# PFC_drivers_v1.net
KiCad netlist of a schematic drawn in EAGLE
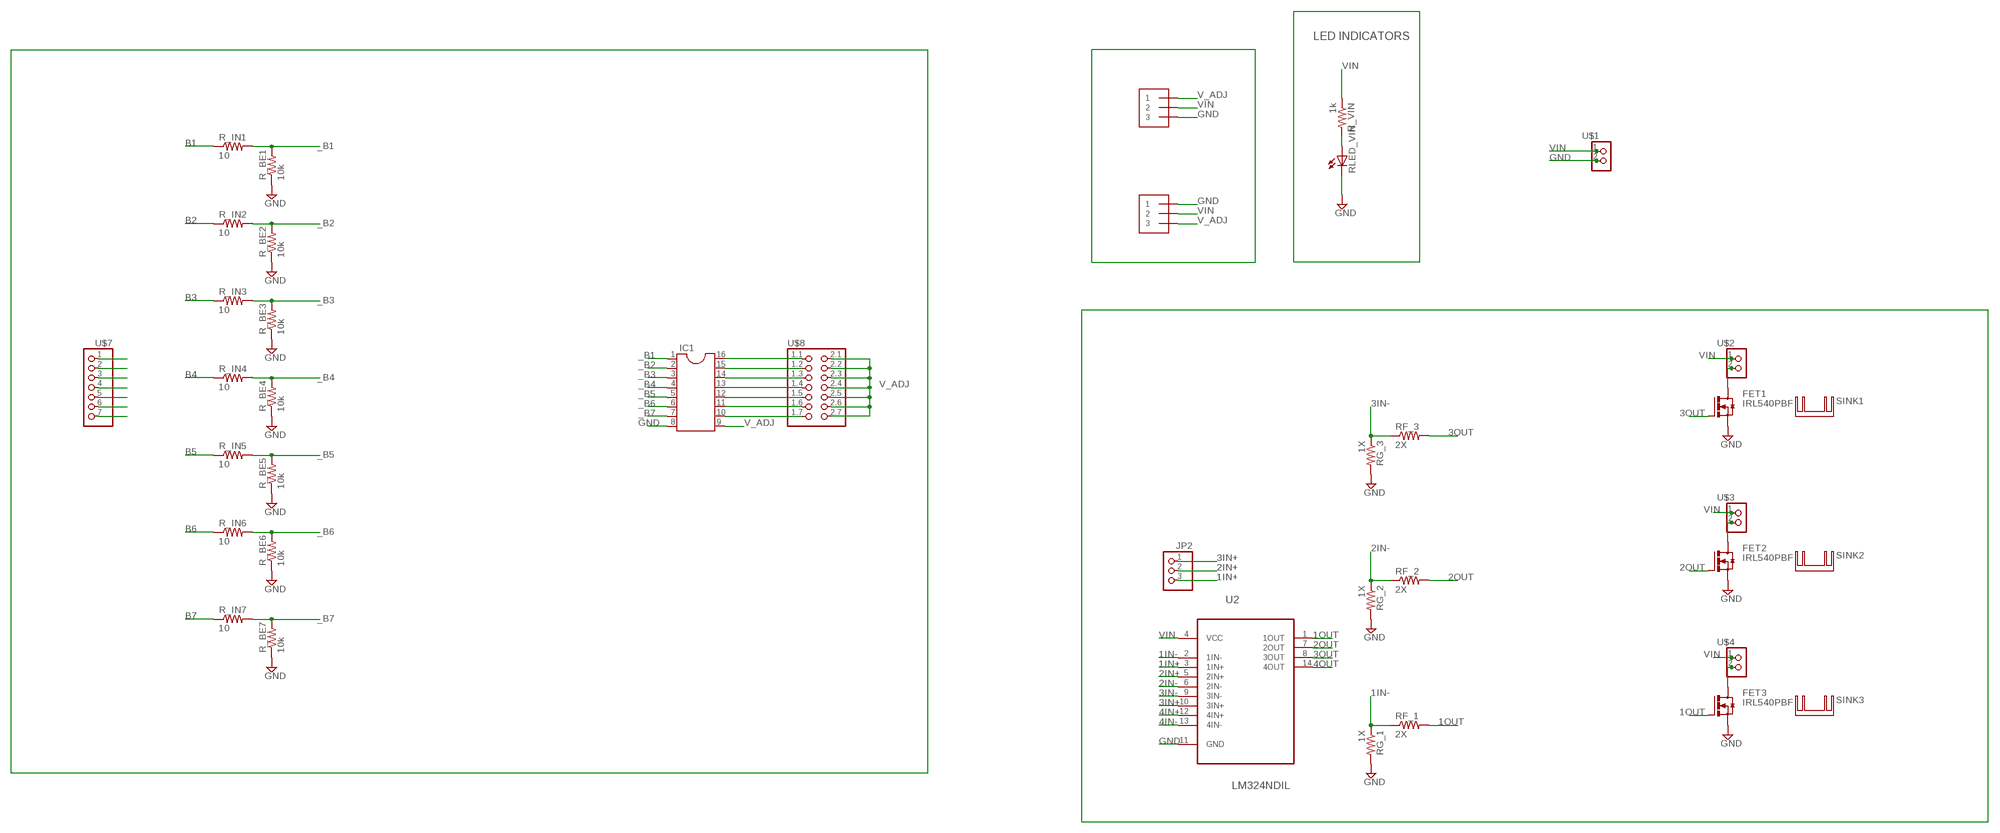
[diagram p0: schematic, sheet 1]

(export (version "E")
  (design (tool "Eeschema 10.0.6"))
  (components
    (comp (ref "FET1")
      (value "IRL540PBF")
      (footprint "eagle-import:TO220AV")
      (libsource (lib "eagle-import") (part "IRL540PBF"))
    )
    (comp (ref "FET2")
      (value "IRL540PBF")
      (footprint "eagle-import:TO220AV")
      (libsource (lib "eagle-import") (part "IRL540PBF"))
    )
    (comp (ref "FET3")
      (value "IRL540PBF")
      (footprint "eagle-import:TO220AV")
      (libsource (lib "eagle-import") (part "IRL540PBF"))
    )
    (comp (ref "IC1")
      (value "DIL16S")
      (footprint "eagle-import:SOCKET-16")
      (libsource (lib "eagle-import") (part "DIL16S"))
    )
    (comp (ref "JP2")
      (value "PINHD-1X3")
      (footprint "eagle-import:1X03")
      (libsource (lib "eagle-import") (part "PINHD-1X3"))
    )
    (comp (ref "RF_1")
      (value "2X")
      (footprint "eagle-import:R0603")
      (libsource (lib "eagle-import") (part "R-US_R0603"))
    )
    (comp (ref "RF_2")
      (value "2X")
      (footprint "eagle-import:R0603")
      (libsource (lib "eagle-import") (part "R-US_R0603"))
    )
    (comp (ref "RF_3")
      (value "2X")
      (footprint "eagle-import:R0603")
      (libsource (lib "eagle-import") (part "R-US_R0603"))
    )
    (comp (ref "RG_1")
      (value "1X")
      (footprint "eagle-import:R0603")
      (libsource (lib "eagle-import") (part "R-US_R0603"))
    )
    (comp (ref "RG_2")
      (value "1X")
      (footprint "eagle-import:R0603")
      (libsource (lib "eagle-import") (part "R-US_R0603"))
    )
    (comp (ref "RG_3")
      (value "1X")
      (footprint "eagle-import:R0603")
      (libsource (lib "eagle-import") (part "R-US_R0603"))
    )
    (comp (ref "RLED_VIN")
      (value "LEDCHIP-LED0603")
      (footprint "eagle-import:CHIP-LED0603")
      (libsource (lib "eagle-import") (part "LEDCHIP-LED0603"))
    )
    (comp (ref "R_BE1")
      (value "10k")
      (footprint "eagle-import:R0603")
      (libsource (lib "eagle-import") (part "R-US_R0603"))
    )
    (comp (ref "R_BE2")
      (value "10k")
      (footprint "eagle-import:R0603")
      (libsource (lib "eagle-import") (part "R-US_R0603"))
    )
    (comp (ref "R_BE3")
      (value "10k")
      (footprint "eagle-import:R0603")
      (libsource (lib "eagle-import") (part "R-US_R0603"))
    )
    (comp (ref "R_BE4")
      (value "10k")
      (footprint "eagle-import:R0603")
      (libsource (lib "eagle-import") (part "R-US_R0603"))
    )
    (comp (ref "R_BE5")
      (value "10k")
      (footprint "eagle-import:R0603")
      (libsource (lib "eagle-import") (part "R-US_R0603"))
    )
    (comp (ref "R_BE6")
      (value "10k")
      (footprint "eagle-import:R0603")
      (libsource (lib "eagle-import") (part "R-US_R0603"))
    )
    (comp (ref "R_BE7")
      (value "10k")
      (footprint "eagle-import:R0603")
      (libsource (lib "eagle-import") (part "R-US_R0603"))
    )
    (comp (ref "R_IN1")
      (value "10")
      (footprint "eagle-import:R0603")
      (libsource (lib "eagle-import") (part "R-US_R0603"))
    )
    (comp (ref "R_IN2")
      (value "10")
      (footprint "eagle-import:R0603")
      (libsource (lib "eagle-import") (part "R-US_R0603"))
    )
    (comp (ref "R_IN3")
      (value "10")
      (footprint "eagle-import:R0603")
      (libsource (lib "eagle-import") (part "R-US_R0603"))
    )
    (comp (ref "R_IN4")
      (value "10")
      (footprint "eagle-import:R0603")
      (libsource (lib "eagle-import") (part "R-US_R0603"))
    )
    (comp (ref "R_IN5")
      (value "10")
      (footprint "eagle-import:R0603")
      (libsource (lib "eagle-import") (part "R-US_R0603"))
    )
    (comp (ref "R_IN6")
      (value "10")
      (footprint "eagle-import:R0603")
      (libsource (lib "eagle-import") (part "R-US_R0603"))
    )
    (comp (ref "R_IN7")
      (value "10")
      (footprint "eagle-import:R0603")
      (libsource (lib "eagle-import") (part "R-US_R0603"))
    )
    (comp (ref "R_VIN")
      (value "1k")
      (footprint "eagle-import:R0603")
      (libsource (lib "eagle-import") (part "R-US_R0603"))
    )
    (comp (ref "SINK1")
      (value "FW1S")
      (footprint "eagle-import:FW1S")
      (libsource (lib "eagle-import") (part "FW1S"))
    )
    (comp (ref "SINK2")
      (value "FW1S")
      (footprint "eagle-import:FW1S")
      (libsource (lib "eagle-import") (part "FW1S"))
    )
    (comp (ref "SINK3")
      (value "FW1S")
      (footprint "eagle-import:FW1S")
      (libsource (lib "eagle-import") (part "FW1S"))
    )
    (comp (ref "U$1")
      (value "PINHD-2X1")
      (footprint "eagle-import:2X01")
      (libsource (lib "eagle-import") (part "PINHD-2X1"))
    )
    (comp (ref "U$2")
      (value "PINHD-2X1")
      (footprint "eagle-import:2X01")
      (libsource (lib "eagle-import") (part "PINHD-2X1"))
    )
    (comp (ref "U$3")
      (value "PINHD-2X1")
      (footprint "eagle-import:2X01")
      (libsource (lib "eagle-import") (part "PINHD-2X1"))
    )
    (comp (ref "U$4")
      (value "PINHD-2X1")
      (footprint "eagle-import:2X01")
      (libsource (lib "eagle-import") (part "PINHD-2X1"))
    )
    (comp (ref "U$5")
      (value "1X3")
      (footprint "eagle-import:1X3-3.5MM")
      (libsource (lib "eagle-import") (part "1X3"))
    )
    (comp (ref "U$6")
      (value "1X3")
      (footprint "eagle-import:1X3-3.5MM")
      (libsource (lib "eagle-import") (part "1X3"))
    )
    (comp (ref "U$7")
      (value "PINHD-1X7")
      (footprint "eagle-import:1X07")
      (libsource (lib "eagle-import") (part "PINHD-1X7"))
    )
    (comp (ref "U$8")
      (value "PINHD-2X7")
      (footprint "eagle-import:2X07-BIG")
      (libsource (lib "eagle-import") (part "PINHD-2X7"))
    )
    (comp (ref "U2")
      (value "LM324NDIL")
      (footprint "eagle-import:DIL14")
      (libsource (lib "eagle-import") (part "LM324NDIL"))
    )
  )
  (nets
    (net (code "1") (name "/1IN+") (class "Default")
      (node (ref "JP2") (pin "3") (pinfunction "3_3") (pintype "passive"))
      (node (ref "U2") (pin "3") (pinfunction "1IN+_3") (pintype "input"))
    )
    (net (code "2") (name "/1IN-") (class "Default")
      (node (ref "RF_1") (pin "1") (pinfunction "1_1") (pintype "passive"))
      (node (ref "RG_1") (pin "1") (pinfunction "1_1") (pintype "passive"))
      (node (ref "U2") (pin "2") (pinfunction "1IN-_2") (pintype "input"))
    )
    (net (code "3") (name "/1OUT") (class "Default")
      (node (ref "FET3") (pin "B") (pinfunction "G_B") (pintype "passive"))
      (node (ref "RF_1") (pin "2") (pinfunction "2_2") (pintype "passive"))
      (node (ref "U2") (pin "1") (pinfunction "1OUT_1") (pintype "output"))
    )
    (net (code "4") (name "/2IN+") (class "Default")
      (node (ref "JP2") (pin "2") (pinfunction "2_2") (pintype "passive"))
      (node (ref "U2") (pin "5") (pinfunction "2IN+_5") (pintype "input"))
    )
    (net (code "5") (name "/2IN-") (class "Default")
      (node (ref "RF_2") (pin "1") (pinfunction "1_1") (pintype "passive"))
      (node (ref "RG_2") (pin "1") (pinfunction "1_1") (pintype "passive"))
      (node (ref "U2") (pin "6") (pinfunction "2IN-_6") (pintype "input"))
    )
    (net (code "6") (name "/2OUT") (class "Default")
      (node (ref "FET2") (pin "B") (pinfunction "G_B") (pintype "passive"))
      (node (ref "RF_2") (pin "2") (pinfunction "2_2") (pintype "passive"))
      (node (ref "U2") (pin "7") (pinfunction "2OUT_7") (pintype "output"))
    )
    (net (code "7") (name "/3IN+") (class "Default")
      (node (ref "JP2") (pin "1") (pinfunction "1_1") (pintype "passive"))
      (node (ref "U2") (pin "10") (pinfunction "3IN+_10") (pintype "input"))
    )
    (net (code "8") (name "/3IN-") (class "Default")
      (node (ref "RF_3") (pin "1") (pinfunction "1_1") (pintype "passive"))
      (node (ref "RG_3") (pin "1") (pinfunction "1_1") (pintype "passive"))
      (node (ref "U2") (pin "9") (pinfunction "3IN-_9") (pintype "input"))
    )
    (net (code "9") (name "/3OUT") (class "Default")
      (node (ref "FET1") (pin "B") (pinfunction "G_B") (pintype "passive"))
      (node (ref "RF_3") (pin "2") (pinfunction "2_2") (pintype "passive"))
      (node (ref "U2") (pin "8") (pinfunction "3OUT_8") (pintype "output"))
    )
    (net (code "10") (name "/4IN+") (class "Default")
      (node (ref "U2") (pin "12") (pinfunction "4IN+_12") (pintype "input"))
    )
    (net (code "11") (name "/4IN-") (class "Default")
      (node (ref "U2") (pin "13") (pinfunction "4IN-_13") (pintype "input"))
    )
    (net (code "12") (name "/4OUT") (class "Default")
      (node (ref "U2") (pin "14") (pinfunction "4OUT_14") (pintype "output"))
    )
    (net (code "13") (name "/B1") (class "Default")
      (node (ref "R_IN1") (pin "1") (pinfunction "1_1") (pintype "passive"))
      (node (ref "U$7") (pin "1") (pinfunction "1_1") (pintype "passive"))
    )
    (net (code "14") (name "/B2") (class "Default")
      (node (ref "R_IN2") (pin "1") (pinfunction "1_1") (pintype "passive"))
      (node (ref "U$7") (pin "2") (pinfunction "2_2") (pintype "passive"))
    )
    (net (code "15") (name "/B3") (class "Default")
      (node (ref "R_IN3") (pin "1") (pinfunction "1_1") (pintype "passive"))
      (node (ref "U$7") (pin "3") (pinfunction "3_3") (pintype "passive"))
    )
    (net (code "16") (name "/B4") (class "Default")
      (node (ref "R_IN4") (pin "1") (pinfunction "1_1") (pintype "passive"))
      (node (ref "U$7") (pin "4") (pinfunction "4_4") (pintype "passive"))
    )
    (net (code "17") (name "/B5") (class "Default")
      (node (ref "R_IN5") (pin "1") (pinfunction "1_1") (pintype "passive"))
      (node (ref "U$7") (pin "5") (pinfunction "5_5") (pintype "passive"))
    )
    (net (code "18") (name "/B6") (class "Default")
      (node (ref "R_IN6") (pin "1") (pinfunction "1_1") (pintype "passive"))
      (node (ref "U$7") (pin "6") (pinfunction "6_6") (pintype "passive"))
    )
    (net (code "19") (name "/B7") (class "Default")
      (node (ref "R_IN7") (pin "1") (pinfunction "1_1") (pintype "passive"))
      (node (ref "U$7") (pin "7") (pinfunction "7_7") (pintype "passive"))
    )
    (net (code "20") (name "/VIN") (class "Default")
      (node (ref "R_VIN") (pin "1") (pinfunction "1_1") (pintype "passive"))
      (node (ref "U$1") (pin "1") (pinfunction "1_1") (pintype "passive"))
      (node (ref "U$2") (pin "1") (pinfunction "1_1") (pintype "passive"))
      (node (ref "U$3") (pin "1") (pinfunction "1_1") (pintype "passive"))
      (node (ref "U$4") (pin "1") (pinfunction "1_1") (pintype "passive"))
      (node (ref "U$5") (pin "2") (pinfunction "2_2") (pintype "passive"))
      (node (ref "U$6") (pin "2") (pinfunction "2_2") (pintype "passive"))
      (node (ref "U2") (pin "4") (pinfunction "VCC_4") (pintype "power_in"))
    )
    (net (code "21") (name "/V_ADJ") (class "Default")
      (node (ref "IC1") (pin "9") (pinfunction "9_9") (pintype "passive"))
      (node (ref "U$5") (pin "1") (pinfunction "1_1") (pintype "passive"))
      (node (ref "U$6") (pin "3") (pinfunction "3_3") (pintype "passive"))
      (node (ref "U$8") (pin "2.1") (pinfunction "2.1_2.1") (pintype "passive"))
      (node (ref "U$8") (pin "2.2") (pinfunction "2.2_2.2") (pintype "passive"))
      (node (ref "U$8") (pin "2.3") (pinfunction "2.3_2.3") (pintype "passive"))
      (node (ref "U$8") (pin "2.4") (pinfunction "2.4_2.4") (pintype "passive"))
      (node (ref "U$8") (pin "2.5") (pinfunction "2.5_2.5") (pintype "passive"))
      (node (ref "U$8") (pin "2.6") (pinfunction "2.6_2.6") (pintype "passive"))
      (node (ref "U$8") (pin "2.7") (pinfunction "2.7_2.7") (pintype "passive"))
    )
    (net (code "22") (name "/_B1") (class "Default")
      (node (ref "IC1") (pin "1") (pinfunction "1_1") (pintype "passive"))
      (node (ref "R_BE1") (pin "2") (pinfunction "2_2") (pintype "passive"))
      (node (ref "R_IN1") (pin "2") (pinfunction "2_2") (pintype "passive"))
    )
    (net (code "23") (name "/_B2") (class "Default")
      (node (ref "IC1") (pin "2") (pinfunction "2_2") (pintype "passive"))
      (node (ref "R_BE2") (pin "2") (pinfunction "2_2") (pintype "passive"))
      (node (ref "R_IN2") (pin "2") (pinfunction "2_2") (pintype "passive"))
    )
    (net (code "24") (name "/_B3") (class "Default")
      (node (ref "IC1") (pin "3") (pinfunction "3_3") (pintype "passive"))
      (node (ref "R_BE3") (pin "2") (pinfunction "2_2") (pintype "passive"))
      (node (ref "R_IN3") (pin "2") (pinfunction "2_2") (pintype "passive"))
    )
    (net (code "25") (name "/_B4") (class "Default")
      (node (ref "IC1") (pin "4") (pinfunction "4_4") (pintype "passive"))
      (node (ref "R_BE4") (pin "2") (pinfunction "2_2") (pintype "passive"))
      (node (ref "R_IN4") (pin "2") (pinfunction "2_2") (pintype "passive"))
    )
    (net (code "26") (name "/_B5") (class "Default")
      (node (ref "IC1") (pin "5") (pinfunction "5_5") (pintype "passive"))
      (node (ref "R_BE5") (pin "2") (pinfunction "2_2") (pintype "passive"))
      (node (ref "R_IN5") (pin "2") (pinfunction "2_2") (pintype "passive"))
    )
    (net (code "27") (name "/_B6") (class "Default")
      (node (ref "IC1") (pin "6") (pinfunction "6_6") (pintype "passive"))
      (node (ref "R_BE6") (pin "2") (pinfunction "2_2") (pintype "passive"))
      (node (ref "R_IN6") (pin "2") (pinfunction "2_2") (pintype "passive"))
    )
    (net (code "28") (name "/_B7") (class "Default")
      (node (ref "IC1") (pin "7") (pinfunction "7_7") (pintype "passive"))
      (node (ref "R_BE7") (pin "2") (pinfunction "2_2") (pintype "passive"))
      (node (ref "R_IN7") (pin "2") (pinfunction "2_2") (pintype "passive"))
    )
    (net (code "29") (name "GND") (class "Default")
      (node (ref "FET1") (pin "E") (pinfunction "S_E") (pintype "passive"))
      (node (ref "FET2") (pin "E") (pinfunction "S_E") (pintype "passive"))
      (node (ref "FET3") (pin "E") (pinfunction "S_E") (pintype "passive"))
      (node (ref "IC1") (pin "8") (pinfunction "8_8") (pintype "passive"))
      (node (ref "RG_1") (pin "2") (pinfunction "2_2") (pintype "passive"))
      (node (ref "RG_2") (pin "2") (pinfunction "2_2") (pintype "passive"))
      (node (ref "RG_3") (pin "2") (pinfunction "2_2") (pintype "passive"))
      (node (ref "RLED_VIN") (pin "C") (pinfunction "C_C") (pintype "passive"))
      (node (ref "R_BE1") (pin "1") (pinfunction "1_1") (pintype "passive"))
      (node (ref "R_BE2") (pin "1") (pinfunction "1_1") (pintype "passive"))
      (node (ref "R_BE3") (pin "1") (pinfunction "1_1") (pintype "passive"))
      (node (ref "R_BE4") (pin "1") (pinfunction "1_1") (pintype "passive"))
      (node (ref "R_BE5") (pin "1") (pinfunction "1_1") (pintype "passive"))
      (node (ref "R_BE6") (pin "1") (pinfunction "1_1") (pintype "passive"))
      (node (ref "R_BE7") (pin "1") (pinfunction "1_1") (pintype "passive"))
      (node (ref "U$1") (pin "2") (pinfunction "3_2") (pintype "passive"))
      (node (ref "U$5") (pin "3") (pinfunction "3_3") (pintype "passive"))
      (node (ref "U$6") (pin "1") (pinfunction "1_1") (pintype "passive"))
      (node (ref "U2") (pin "11") (pinfunction "GND_11") (pintype "passive"))
    )
    (net (code "30") (name "Net-(FET1-D)") (class "Default")
      (node (ref "FET1") (pin "C") (pinfunction "D_C") (pintype "passive"))
      (node (ref "U$2") (pin "2") (pinfunction "3_2") (pintype "passive"))
    )
    (net (code "31") (name "Net-(FET2-D)") (class "Default")
      (node (ref "FET2") (pin "C") (pinfunction "D_C") (pintype "passive"))
      (node (ref "U$3") (pin "2") (pinfunction "3_2") (pintype "passive"))
    )
    (net (code "32") (name "Net-(FET3-D)") (class "Default")
      (node (ref "FET3") (pin "C") (pinfunction "D_C") (pintype "passive"))
      (node (ref "U$4") (pin "2") (pinfunction "3_2") (pintype "passive"))
    )
    (net (code "33") (name "Net-(IC1-Pad10)") (class "Default")
      (node (ref "IC1") (pin "10") (pinfunction "10_10") (pintype "passive"))
      (node (ref "U$8") (pin "1.7") (pinfunction "1.7_1.7") (pintype "passive"))
    )
    (net (code "34") (name "Net-(IC1-Pad11)") (class "Default")
      (node (ref "IC1") (pin "11") (pinfunction "11_11") (pintype "passive"))
      (node (ref "U$8") (pin "1.6") (pinfunction "1.6_1.6") (pintype "passive"))
    )
    (net (code "35") (name "Net-(IC1-Pad12)") (class "Default")
      (node (ref "IC1") (pin "12") (pinfunction "12_12") (pintype "passive"))
      (node (ref "U$8") (pin "1.5") (pinfunction "1.5_1.5") (pintype "passive"))
    )
    (net (code "36") (name "Net-(IC1-Pad13)") (class "Default")
      (node (ref "IC1") (pin "13") (pinfunction "13_13") (pintype "passive"))
      (node (ref "U$8") (pin "1.4") (pinfunction "1.4_1.4") (pintype "passive"))
    )
    (net (code "37") (name "Net-(IC1-Pad14)") (class "Default")
      (node (ref "IC1") (pin "14") (pinfunction "14_14") (pintype "passive"))
      (node (ref "U$8") (pin "1.3") (pinfunction "1.3_1.3") (pintype "passive"))
    )
    (net (code "38") (name "Net-(IC1-Pad15)") (class "Default")
      (node (ref "IC1") (pin "15") (pinfunction "15_15") (pintype "passive"))
      (node (ref "U$8") (pin "1.2") (pinfunction "1.2_1.2") (pintype "passive"))
    )
    (net (code "39") (name "Net-(IC1-Pad16)") (class "Default")
      (node (ref "IC1") (pin "16") (pinfunction "16_16") (pintype "passive"))
      (node (ref "U$8") (pin "1.1") (pinfunction "1.1_1.1") (pintype "passive"))
    )
    (net (code "40") (name "Net-(RLED_VIN-PadA)") (class "Default")
      (node (ref "RLED_VIN") (pin "A") (pinfunction "A_A") (pintype "passive"))
      (node (ref "R_VIN") (pin "2") (pinfunction "2_2") (pintype "passive"))
    )
  )
)
